# I2C_Sensor.net
KiCad netlist of a schematic drawn in Altium Designer
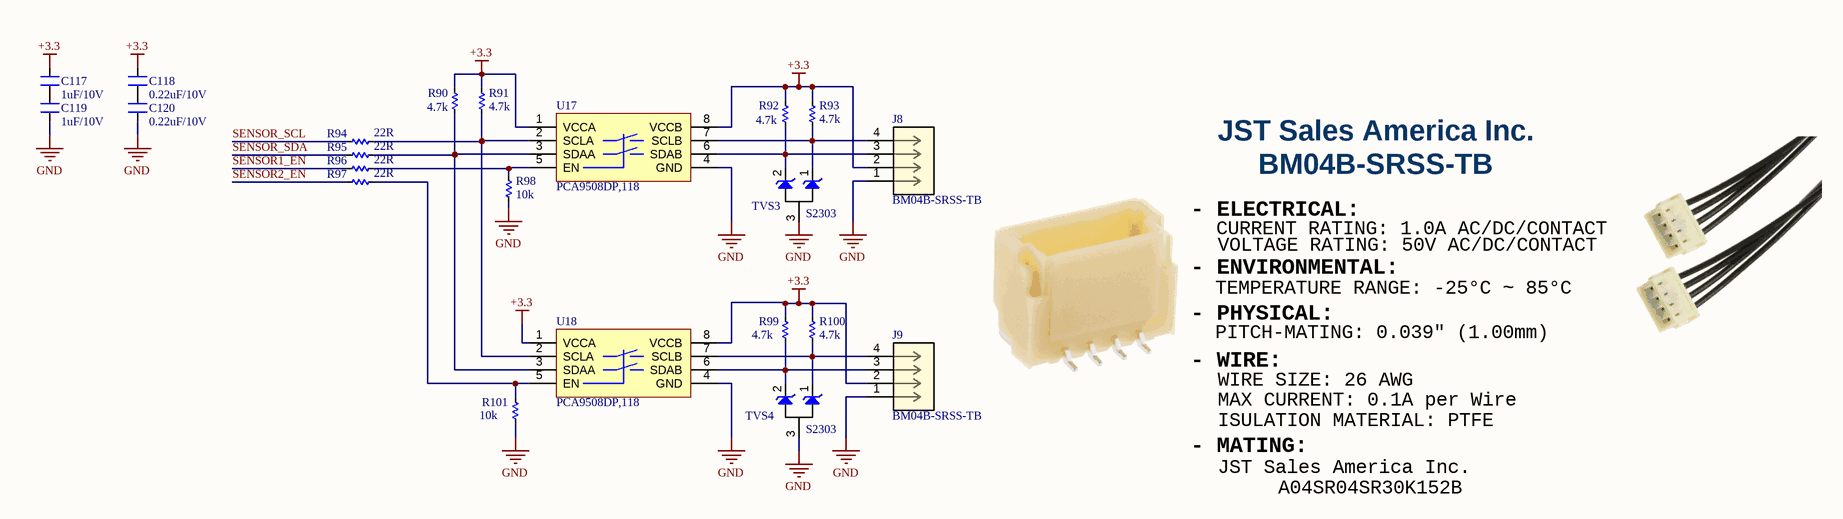
[diagram p0: I2C_Sensor.SchDoc]

(export (version "E")
  (design (tool "Eeschema 10.0.6"))
  (components
    (comp (ref "C117")
      (value "1uF/10V")
      (footprint "CAP_C_1608X80")
      (libsource (lib "Sang_library") (part "Capacitors"))
    )
    (comp (ref "C118")
      (value "0.22uF/10V")
      (footprint "CAP_C_1608X80")
      (libsource (lib "Sang_library") (part "Capacitors"))
    )
    (comp (ref "C119")
      (value "1uF/10V")
      (footprint "CAP_C_1608X80")
      (libsource (lib "Sang_library") (part "Capacitors"))
    )
    (comp (ref "C120")
      (value "0.22uF/10V")
      (footprint "CAP_C_1608X80")
      (libsource (lib "Sang_library") (part "Capacitors"))
    )
    (comp (ref "J8")
      (value "BM04B-SRSS-TB")
      (footprint "BM04B-SRSS-TB")
      (description "CONN HEADER SMD 4POS 1MM")
      (libsource (lib "Sang_library") (part "BM04B-SRSS-TB"))
    )
    (comp (ref "J9")
      (value "BM04B-SRSS-TB")
      (footprint "BM04B-SRSS-TB")
      (description "CONN HEADER SMD 4POS 1MM")
      (libsource (lib "Sang_library") (part "BM04B-SRSS-TB"))
    )
    (comp (ref "R90")
      (value "4.7k")
      (footprint "RES_C_1608X60")
      (description "SMD")
      (fields
        (field (name "MANUFACTURER") "Generic Components")
        (field (name "PUBLISHER") "Altium Hobart Technology Centre")
      )
      (libsource (lib "Sang_library") (part "Res SMD"))
    )
    (comp (ref "R91")
      (value "4.7k")
      (footprint "RES_C_1608X60")
      (description "SMD")
      (fields
        (field (name "MANUFACTURER") "Generic Components")
        (field (name "PUBLISHER") "Altium Hobart Technology Centre")
      )
      (libsource (lib "Sang_library") (part "Res SMD"))
    )
    (comp (ref "R92")
      (value "4.7k")
      (footprint "RES_C_1608X60")
      (description "SMD")
      (fields
        (field (name "MANUFACTURER") "Generic Components")
        (field (name "PUBLISHER") "Altium Hobart Technology Centre")
      )
      (libsource (lib "Sang_library") (part "Res SMD"))
    )
    (comp (ref "R93")
      (value "4.7k")
      (footprint "RES_C_1608X60")
      (description "SMD")
      (fields
        (field (name "MANUFACTURER") "Generic Components")
        (field (name "PUBLISHER") "Altium Hobart Technology Centre")
      )
      (libsource (lib "Sang_library") (part "Res SMD"))
    )
    (comp (ref "R94")
      (value "22R")
      (footprint "RES_C_1608X60")
      (description "SMD")
      (fields
        (field (name "MANUFACTURER") "Generic Components")
        (field (name "PUBLISHER") "Altium Hobart Technology Centre")
      )
      (libsource (lib "Sang_library") (part "Res SMD"))
    )
    (comp (ref "R95")
      (value "22R")
      (footprint "RES_C_1608X60")
      (description "SMD")
      (fields
        (field (name "MANUFACTURER") "Generic Components")
        (field (name "PUBLISHER") "Altium Hobart Technology Centre")
      )
      (libsource (lib "Sang_library") (part "Res SMD"))
    )
    (comp (ref "R96")
      (value "22R")
      (footprint "RES_C_1608X60")
      (description "SMD")
      (fields
        (field (name "MANUFACTURER") "Generic Components")
        (field (name "PUBLISHER") "Altium Hobart Technology Centre")
      )
      (libsource (lib "Sang_library") (part "Res SMD"))
    )
    (comp (ref "R97")
      (value "22R")
      (footprint "RES_C_1608X60")
      (description "SMD")
      (fields
        (field (name "MANUFACTURER") "Generic Components")
        (field (name "PUBLISHER") "Altium Hobart Technology Centre")
      )
      (libsource (lib "Sang_library") (part "Res SMD"))
    )
    (comp (ref "R98")
      (value "10k")
      (footprint "RES_C_1608X60")
      (description "SMD")
      (fields
        (field (name "MANUFACTURER") "Generic Components")
        (field (name "PUBLISHER") "Altium Hobart Technology Centre")
      )
      (libsource (lib "Sang_library") (part "Res SMD"))
    )
    (comp (ref "R99")
      (value "4.7k")
      (footprint "RES_C_1608X60")
      (description "SMD")
      (fields
        (field (name "MANUFACTURER") "Generic Components")
        (field (name "PUBLISHER") "Altium Hobart Technology Centre")
      )
      (libsource (lib "Sang_library") (part "Res SMD"))
    )
    (comp (ref "R100")
      (value "4.7k")
      (footprint "RES_C_1608X60")
      (description "SMD")
      (fields
        (field (name "MANUFACTURER") "Generic Components")
        (field (name "PUBLISHER") "Altium Hobart Technology Centre")
      )
      (libsource (lib "Sang_library") (part "Res SMD"))
    )
    (comp (ref "R101")
      (value "10k")
      (footprint "RES_C_1608X60")
      (description "SMD")
      (fields
        (field (name "MANUFACTURER") "Generic Components")
        (field (name "PUBLISHER") "Altium Hobart Technology Centre")
      )
      (libsource (lib "Sang_library") (part "Res SMD"))
    )
    (comp (ref "TVS3")
      (value "S2303")
      (footprint "sot23-12_3_EXP_V110")
      (description "TVS DIODE 3.3VWM 8VC SOT233")
      (libsource (lib "Sang_library") (part "S2305"))
    )
    (comp (ref "TVS4")
      (value "S2303")
      (footprint "sot23-12_3_EXP_V110")
      (description "TVS DIODE 3.3VWM 8VC SOT233")
      (libsource (lib "Sang_library") (part "S2305"))
    )
    (comp (ref "U17")
      (value "PCA9508DP,118")
      (footprint "TSOP8")
      (libsource (lib "Sang_library") (part "PCA9508DP,118"))
    )
    (comp (ref "U18")
      (value "PCA9508DP,118")
      (footprint "TSOP8")
      (libsource (lib "Sang_library") (part "PCA9508DP,118"))
    )
  )
  (nets
    (net (code "1") (name "+3.3") (class "Default")
      (node (ref "C117") (pin "2") (pinfunction "2_2") (pintype "passive"))
      (node (ref "C118") (pin "2") (pinfunction "2_2") (pintype "passive"))
      (node (ref "J8") (pin "2") (pinfunction "2_2") (pintype "passive"))
      (node (ref "J9") (pin "2") (pinfunction "2_2") (pintype "passive"))
      (node (ref "R100") (pin "1") (pinfunction "1_1") (pintype "passive"))
      (node (ref "R90") (pin "1") (pinfunction "1_1") (pintype "passive"))
      (node (ref "R91") (pin "1") (pinfunction "1_1") (pintype "passive"))
      (node (ref "R92") (pin "1") (pinfunction "1_1") (pintype "passive"))
      (node (ref "R93") (pin "1") (pinfunction "1_1") (pintype "passive"))
      (node (ref "R99") (pin "1") (pinfunction "1_1") (pintype "passive"))
      (node (ref "U17") (pin "1") (pinfunction "VCCA_1") (pintype "passive"))
      (node (ref "U17") (pin "8") (pinfunction "VCCB_8") (pintype "passive"))
      (node (ref "U18") (pin "1") (pinfunction "VCCA_1") (pintype "passive"))
      (node (ref "U18") (pin "8") (pinfunction "VCCB_8") (pintype "passive"))
    )
    (net (code "2") (name "/SENSOR1_EN") (class "Default")
      (node (ref "R96") (pin "1") (pinfunction "1_1") (pintype "passive"))
    )
    (net (code "3") (name "/SENSOR2_EN") (class "Default")
      (node (ref "R97") (pin "1") (pinfunction "1_1") (pintype "passive"))
    )
    (net (code "4") (name "/SENSOR_SCL") (class "Default")
      (node (ref "R94") (pin "1") (pinfunction "1_1") (pintype "passive"))
    )
    (net (code "5") (name "/SENSOR_SDA") (class "Default")
      (node (ref "R95") (pin "1") (pinfunction "1_1") (pintype "passive"))
    )
    (net (code "6") (name "GND") (class "Default")
      (node (ref "C119") (pin "1") (pinfunction "1_1") (pintype "passive"))
      (node (ref "C120") (pin "1") (pinfunction "1_1") (pintype "passive"))
      (node (ref "J8") (pin "1") (pinfunction "1_1") (pintype "passive"))
      (node (ref "J9") (pin "1") (pinfunction "1_1") (pintype "passive"))
      (node (ref "R101") (pin "2") (pinfunction "2_2") (pintype "passive"))
      (node (ref "R98") (pin "2") (pinfunction "2_2") (pintype "passive"))
      (node (ref "TVS3") (pin "3") (pinfunction "3_3") (pintype "passive"))
      (node (ref "TVS4") (pin "3") (pinfunction "3_3") (pintype "passive"))
      (node (ref "U17") (pin "4") (pinfunction "GND_4") (pintype "passive"))
      (node (ref "U18") (pin "4") (pinfunction "GND_4") (pintype "passive"))
    )
    (net (code "7") (name "Net-(C117-Pad1)") (class "Default")
      (node (ref "C117") (pin "1") (pinfunction "1_1") (pintype "passive"))
      (node (ref "C119") (pin "2") (pinfunction "2_2") (pintype "passive"))
    )
    (net (code "8") (name "Net-(C118-Pad1)") (class "Default")
      (node (ref "C118") (pin "1") (pinfunction "1_1") (pintype "passive"))
      (node (ref "C120") (pin "2") (pinfunction "2_2") (pintype "passive"))
    )
    (net (code "9") (name "Net-(U17-EN)") (class "Default")
      (node (ref "R96") (pin "2") (pinfunction "2_2") (pintype "passive"))
      (node (ref "R98") (pin "1") (pinfunction "1_1") (pintype "passive"))
      (node (ref "U17") (pin "5") (pinfunction "EN_5") (pintype "passive"))
    )
    (net (code "10") (name "Net-(U17-SCLA)") (class "Default")
      (node (ref "R91") (pin "2") (pinfunction "2_2") (pintype "passive"))
      (node (ref "R94") (pin "2") (pinfunction "2_2") (pintype "passive"))
      (node (ref "U17") (pin "2") (pinfunction "SCLA_2") (pintype "passive"))
      (node (ref "U18") (pin "2") (pinfunction "SCLA_2") (pintype "passive"))
    )
    (net (code "11") (name "Net-(U17-SCLB)") (class "Default")
      (node (ref "J8") (pin "4") (pinfunction "4_4") (pintype "passive"))
      (node (ref "R93") (pin "2") (pinfunction "2_2") (pintype "passive"))
      (node (ref "TVS3") (pin "1") (pinfunction "1_1") (pintype "passive"))
      (node (ref "U17") (pin "7") (pinfunction "SCLB_7") (pintype "passive"))
    )
    (net (code "12") (name "Net-(U17-SDAA)") (class "Default")
      (node (ref "R90") (pin "2") (pinfunction "2_2") (pintype "passive"))
      (node (ref "R95") (pin "2") (pinfunction "2_2") (pintype "passive"))
      (node (ref "U17") (pin "3") (pinfunction "SDAA_3") (pintype "passive"))
      (node (ref "U18") (pin "3") (pinfunction "SDAA_3") (pintype "passive"))
    )
    (net (code "13") (name "Net-(U17-SDAB)") (class "Default")
      (node (ref "J8") (pin "3") (pinfunction "3_3") (pintype "passive"))
      (node (ref "R92") (pin "2") (pinfunction "2_2") (pintype "passive"))
      (node (ref "TVS3") (pin "2") (pinfunction "2_2") (pintype "passive"))
      (node (ref "U17") (pin "6") (pinfunction "SDAB_6") (pintype "passive"))
    )
    (net (code "14") (name "Net-(U18-EN)") (class "Default")
      (node (ref "R101") (pin "1") (pinfunction "1_1") (pintype "passive"))
      (node (ref "R97") (pin "2") (pinfunction "2_2") (pintype "passive"))
      (node (ref "U18") (pin "5") (pinfunction "EN_5") (pintype "passive"))
    )
    (net (code "15") (name "Net-(U18-SCLB)") (class "Default")
      (node (ref "J9") (pin "4") (pinfunction "4_4") (pintype "passive"))
      (node (ref "R100") (pin "2") (pinfunction "2_2") (pintype "passive"))
      (node (ref "TVS4") (pin "1") (pinfunction "1_1") (pintype "passive"))
      (node (ref "U18") (pin "7") (pinfunction "SCLB_7") (pintype "passive"))
    )
    (net (code "16") (name "Net-(U18-SDAB)") (class "Default")
      (node (ref "J9") (pin "3") (pinfunction "3_3") (pintype "passive"))
      (node (ref "R99") (pin "2") (pinfunction "2_2") (pintype "passive"))
      (node (ref "TVS4") (pin "2") (pinfunction "2_2") (pintype "passive"))
      (node (ref "U18") (pin "6") (pinfunction "SDAB_6") (pintype "passive"))
    )
  )
)
